# kiln_rpi_breakout_atmega328.net
KiCad netlist of a schematic drawn in EAGLE
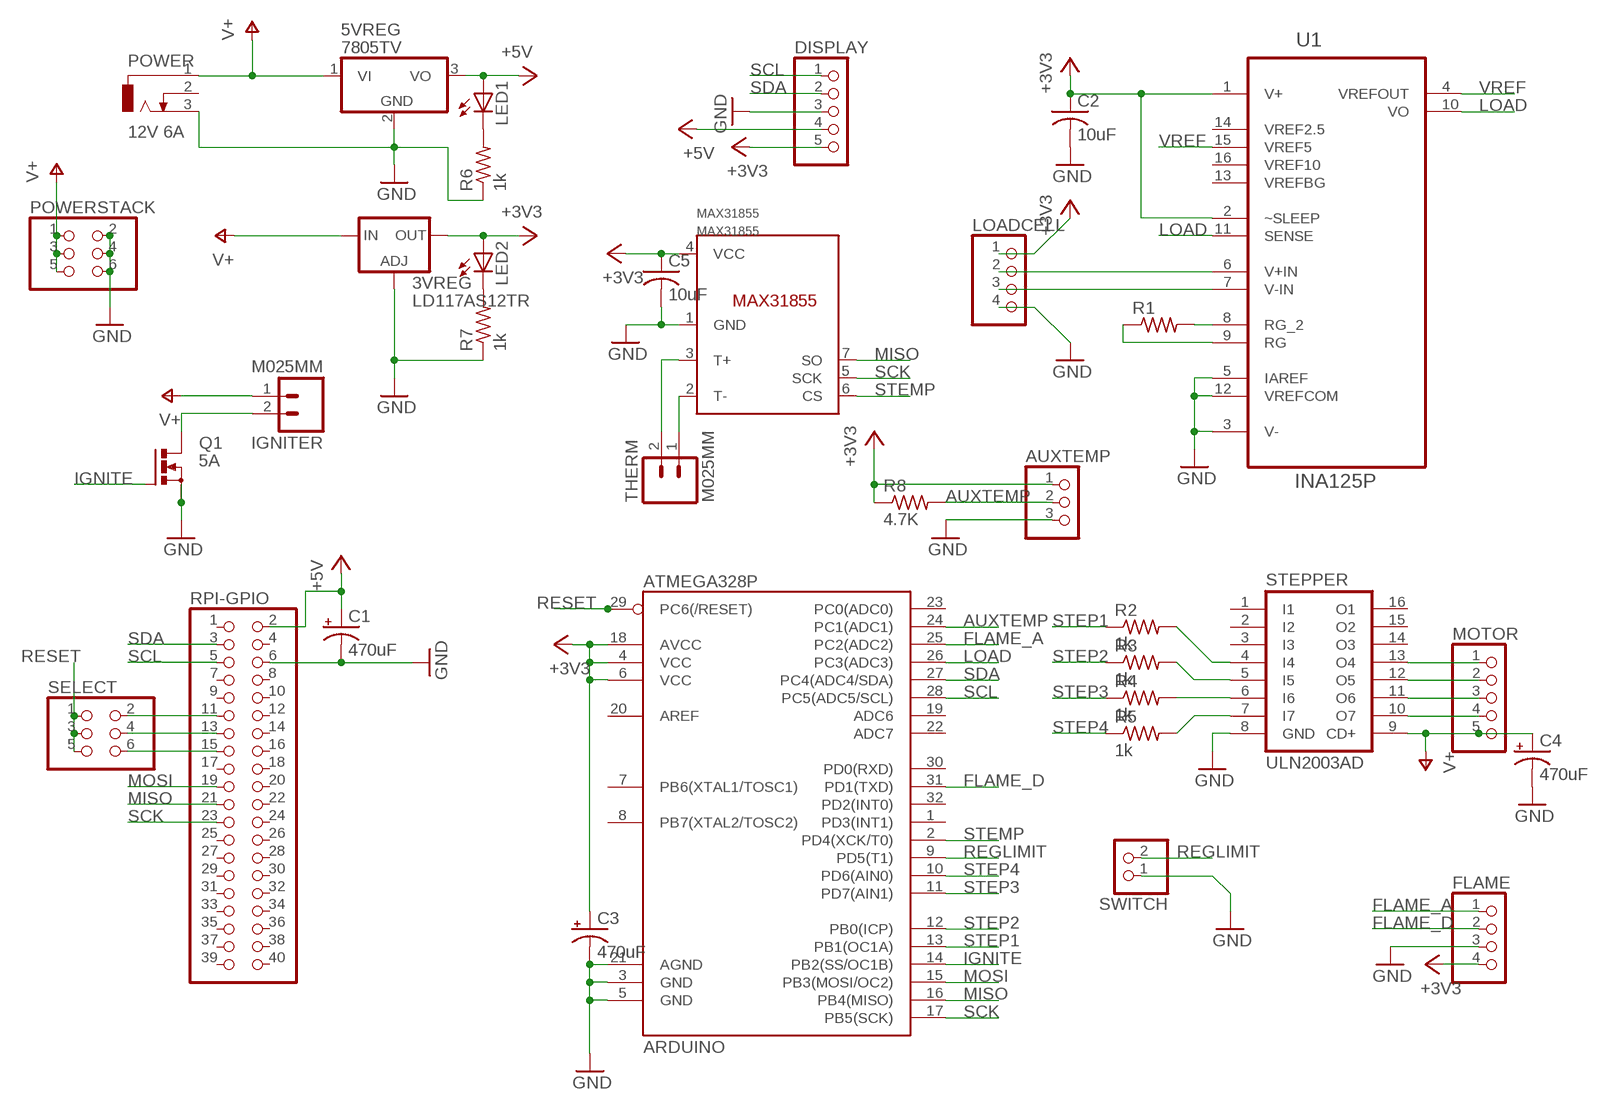
[diagram p0: schematic, sheet 1]

(export (version "E")
  (design (tool "Eeschema 10.0.6"))
  (components
    (comp (ref "3VREG")
      (value "LD117AS12TR")
      (footprint "eagle-import:SOT223")
      (libsource (lib "eagle-import") (part "LD117A?S12TR"))
    )
    (comp (ref "5VREG")
      (value "7805TV")
      (footprint "eagle-import:TO220V")
      (libsource (lib "eagle-import") (part "78TV05"))
    )
    (comp (ref "ARDUINO")
      (value "ATMEGA328P")
      (footprint "eagle-import:TQFP32-08")
      (libsource (lib "eagle-import") (part "ATMEGA328_SMT"))
    )
    (comp (ref "AUXTEMP")
      (value "PINHD-1X3")
      (footprint "eagle-import:1X03")
      (libsource (lib "eagle-import") (part "PINHD-1X3"))
    )
    (comp (ref "C1")
      (value "470uF")
      (footprint "eagle-import:E3,5-8")
      (libsource (lib "eagle-import") (part "CPOL-USE3.5-8"))
    )
    (comp (ref "C2")
      (value "10uF")
      (footprint "eagle-import:C025-030X050")
      (libsource (lib "eagle-import") (part "C-US025-030X050"))
    )
    (comp (ref "C3")
      (value "470uF")
      (footprint "eagle-import:E3,5-8")
      (libsource (lib "eagle-import") (part "CPOL-USE3.5-8"))
    )
    (comp (ref "C4")
      (value "470uF")
      (footprint "eagle-import:E3,5-8")
      (libsource (lib "eagle-import") (part "CPOL-USE3.5-8"))
    )
    (comp (ref "C5")
      (value "10uF")
      (footprint "eagle-import:C025-030X050")
      (libsource (lib "eagle-import") (part "C-US025-030X050"))
    )
    (comp (ref "DISPLAY")
      (value "PINHD-1X5")
      (footprint "eagle-import:1X05")
      (libsource (lib "eagle-import") (part "PINHD-1X5"))
    )
    (comp (ref "FLAME")
      (value "PINHD-1X4/90")
      (footprint "eagle-import:1X04_90")
      (libsource (lib "eagle-import") (part "PINHD-1X4/90"))
    )
    (comp (ref "IGNITER")
      (value "M025MM")
      (footprint "eagle-import:SCREWTERMINAL-5MM-2")
      (libsource (lib "eagle-import") (part "M025MM"))
    )
    (comp (ref "LED1")
      (value "LED3MM")
      (footprint "eagle-import:LED3MM")
      (libsource (lib "eagle-import") (part "LED3MM"))
    )
    (comp (ref "LED2")
      (value "LED3MM")
      (footprint "eagle-import:LED3MM")
      (libsource (lib "eagle-import") (part "LED3MM"))
    )
    (comp (ref "LOADCELL")
      (value "PINHD-1X4/90")
      (footprint "eagle-import:1X04_90")
      (libsource (lib "eagle-import") (part "PINHD-1X4/90"))
    )
    (comp (ref "MAX31855")
      (value "MAX31855")
      (footprint "eagle-import:SOIC8")
      (libsource (lib "eagle-import") (part "MAX31855"))
    )
    (comp (ref "MOTOR")
      (value "PINHD-1X5/90")
      (footprint "eagle-import:1X05_90")
      (libsource (lib "eagle-import") (part "PINHD-1X5/90"))
    )
    (comp (ref "POWER")
      (value "12V 6A")
      (footprint "eagle-import:DCJ0303")
      (libsource (lib "eagle-import") (part "DCJ0303"))
    )
    (comp (ref "POWERSTACK")
      (value "PINHD-2X3")
      (footprint "eagle-import:2X03")
      (libsource (lib "eagle-import") (part "PINHD-2X3"))
    )
    (comp (ref "Q1")
      (value "5A")
      (footprint "eagle-import:TO220BV")
      (libsource (lib "eagle-import") (part "PMOSFET_NTO220BV"))
    )
    (comp (ref "R1")
      (value "R-US_0204/7")
      (footprint "eagle-import:0204_7")
      (libsource (lib "eagle-import") (part "R-US_0204/7"))
    )
    (comp (ref "R2")
      (value "1k")
      (footprint "eagle-import:0207_7")
      (libsource (lib "eagle-import") (part "R-US_0207/7"))
    )
    (comp (ref "R3")
      (value "1k")
      (footprint "eagle-import:0207_7")
      (libsource (lib "eagle-import") (part "R-US_0207/7"))
    )
    (comp (ref "R4")
      (value "1k")
      (footprint "eagle-import:0207_7")
      (libsource (lib "eagle-import") (part "R-US_0207/7"))
    )
    (comp (ref "R5")
      (value "1k")
      (footprint "eagle-import:0207_7")
      (libsource (lib "eagle-import") (part "R-US_0207/7"))
    )
    (comp (ref "R6")
      (value "1k")
      (footprint "eagle-import:0207_7")
      (libsource (lib "eagle-import") (part "R-US_0207/7"))
    )
    (comp (ref "R7")
      (value "1k")
      (footprint "eagle-import:0207_7")
      (libsource (lib "eagle-import") (part "R-US_0207/7"))
    )
    (comp (ref "R8")
      (value "4.7K")
      (footprint "eagle-import:0207_2V")
      (libsource (lib "eagle-import") (part "R-US_0207/2V"))
    )
    (comp (ref "RPI-GPIO")
      (value "PINHD-2X20")
      (footprint "eagle-import:2X20")
      (libsource (lib "eagle-import") (part "PINHD-2X20"))
    )
    (comp (ref "SELECT")
      (value "PINHD-2X3")
      (footprint "eagle-import:2X03")
      (libsource (lib "eagle-import") (part "PINHD-2X3"))
    )
    (comp (ref "STEPPER")
      (value "ULN2003AD")
      (footprint "eagle-import:SO16")
      (libsource (lib "eagle-import") (part "ULN2003AD"))
    )
    (comp (ref "SWITCH")
      (value "PINHD-1X2/90")
      (footprint "eagle-import:1X02_90")
      (libsource (lib "eagle-import") (part "PINHD-1X2/90"))
    )
    (comp (ref "THERM")
      (value "M025MM")
      (footprint "eagle-import:SCREWTERMINAL-5MM-2")
      (libsource (lib "eagle-import") (part "M025MM"))
    )
    (comp (ref "U1")
      (value "INA125P")
      (footprint "eagle-import:DIP254P762X508-16")
      (libsource (lib "eagle-import") (part "INA125P"))
    )
  )
  (nets
    (net (code "1") (name "+3V3") (class "Default")
      (node (ref "3VREG") (pin "4") (pinfunction "OUT_4") (pintype "passive"))
      (node (ref "ARDUINO") (pin "18") (pinfunction "AVCC_18") (pintype "bidirectional"))
      (node (ref "ARDUINO") (pin "4") (pinfunction "VCC_4") (pintype "bidirectional"))
      (node (ref "ARDUINO") (pin "6") (pinfunction "VCC_6") (pintype "bidirectional"))
      (node (ref "AUXTEMP") (pin "1") (pinfunction "1_1") (pintype "passive"))
      (node (ref "C2") (pin "1") (pinfunction "1_1") (pintype "passive"))
      (node (ref "C3") (pin "+") (pinfunction "+_+") (pintype "passive"))
      (node (ref "C5") (pin "1") (pinfunction "1_1") (pintype "passive"))
      (node (ref "DISPLAY") (pin "5") (pinfunction "5_5") (pintype "passive"))
      (node (ref "FLAME") (pin "4") (pinfunction "4_4") (pintype "passive"))
      (node (ref "LED2") (pin "A") (pinfunction "A_A") (pintype "passive"))
      (node (ref "LOADCELL") (pin "1") (pinfunction "1_1") (pintype "passive"))
      (node (ref "MAX31855") (pin "4") (pinfunction "VCC_4") (pintype "power_in"))
      (node (ref "R8") (pin "1") (pinfunction "1_1") (pintype "passive"))
      (node (ref "U1") (pin "1") (pinfunction "V+_1") (pintype "power_in"))
      (node (ref "U1") (pin "2") (pinfunction "~{SLEEP}_2") (pintype "passive"))
    )
    (net (code "2") (name "+5V") (class "Default")
      (node (ref "5VREG") (pin "3") (pinfunction "VO_3") (pintype "passive"))
      (node (ref "C1") (pin "+") (pinfunction "+_+") (pintype "passive"))
      (node (ref "DISPLAY") (pin "4") (pinfunction "4_4") (pintype "passive"))
      (node (ref "LED1") (pin "A") (pinfunction "A_A") (pintype "passive"))
      (node (ref "RPI-GPIO") (pin "2") (pinfunction "2_2") (pintype "passive"))
    )
    (net (code "3") (name "/AUXTEMP") (class "Default")
      (node (ref "ARDUINO") (pin "24") (pinfunction "PC1(ADC1)_24") (pintype "bidirectional"))
      (node (ref "AUXTEMP") (pin "2") (pinfunction "2_2") (pintype "passive"))
      (node (ref "R8") (pin "2") (pinfunction "2_2") (pintype "passive"))
    )
    (net (code "4") (name "/FLAME_A") (class "Default")
      (node (ref "ARDUINO") (pin "25") (pinfunction "PC2(ADC2)_25") (pintype "bidirectional"))
      (node (ref "FLAME") (pin "1") (pinfunction "1_1") (pintype "passive"))
    )
    (net (code "5") (name "/FLAME_D") (class "Default")
      (node (ref "ARDUINO") (pin "31") (pinfunction "PD1(TXD)_31") (pintype "bidirectional"))
      (node (ref "FLAME") (pin "2") (pinfunction "2_2") (pintype "passive"))
    )
    (net (code "6") (name "/IGNITE") (class "Default")
      (node (ref "ARDUINO") (pin "14") (pinfunction "PB2(SS/OC1B)_14") (pintype "bidirectional"))
      (node (ref "Q1") (pin "G") (pinfunction "G_G") (pintype "passive"))
    )
    (net (code "7") (name "/LOAD") (class "Default")
      (node (ref "ARDUINO") (pin "26") (pinfunction "PC3(ADC3)_26") (pintype "bidirectional"))
      (node (ref "U1") (pin "10") (pinfunction "VO_10") (pintype "output"))
      (node (ref "U1") (pin "11") (pinfunction "SENSE_11") (pintype "input"))
    )
    (net (code "8") (name "/MISO") (class "Default")
      (node (ref "ARDUINO") (pin "16") (pinfunction "PB4(MISO)_16") (pintype "bidirectional"))
      (node (ref "MAX31855") (pin "7") (pinfunction "SO_7") (pintype "output"))
      (node (ref "RPI-GPIO") (pin "21") (pinfunction "21_21") (pintype "passive"))
    )
    (net (code "9") (name "/MOSI") (class "Default")
      (node (ref "ARDUINO") (pin "15") (pinfunction "PB3(MOSI/OC2)_15") (pintype "bidirectional"))
      (node (ref "RPI-GPIO") (pin "19") (pinfunction "19_19") (pintype "passive"))
    )
    (net (code "10") (name "/REGLIMIT") (class "Default")
      (node (ref "ARDUINO") (pin "9") (pinfunction "PD5(T1)_9") (pintype "bidirectional"))
      (node (ref "SWITCH") (pin "2") (pinfunction "2_2") (pintype "passive"))
    )
    (net (code "11") (name "/RESET") (class "Default")
      (node (ref "ARDUINO") (pin "29") (pinfunction "PC6(/RESET)_29") (pintype "bidirectional"))
      (node (ref "SELECT") (pin "1") (pinfunction "1_1") (pintype "passive"))
      (node (ref "SELECT") (pin "3") (pinfunction "3_3") (pintype "passive"))
      (node (ref "SELECT") (pin "5") (pinfunction "5_5") (pintype "passive"))
    )
    (net (code "12") (name "/SCK") (class "Default")
      (node (ref "ARDUINO") (pin "17") (pinfunction "PB5(SCK)_17") (pintype "bidirectional"))
      (node (ref "MAX31855") (pin "5") (pinfunction "SCK_5") (pintype "input"))
      (node (ref "RPI-GPIO") (pin "23") (pinfunction "23_23") (pintype "passive"))
    )
    (net (code "13") (name "/SCL") (class "Default")
      (node (ref "ARDUINO") (pin "28") (pinfunction "PC5(ADC5/SCL)_28") (pintype "bidirectional"))
      (node (ref "DISPLAY") (pin "1") (pinfunction "1_1") (pintype "passive"))
      (node (ref "RPI-GPIO") (pin "5") (pinfunction "5_5") (pintype "passive"))
    )
    (net (code "14") (name "/SDA") (class "Default")
      (node (ref "ARDUINO") (pin "27") (pinfunction "PC4(ADC4/SDA)_27") (pintype "bidirectional"))
      (node (ref "DISPLAY") (pin "2") (pinfunction "2_2") (pintype "passive"))
      (node (ref "RPI-GPIO") (pin "3") (pinfunction "3_3") (pintype "passive"))
    )
    (net (code "15") (name "/STEMP") (class "Default")
      (node (ref "ARDUINO") (pin "2") (pinfunction "PD4(XCK/T0)_2") (pintype "bidirectional"))
      (node (ref "MAX31855") (pin "6") (pinfunction "CS_6") (pintype "input"))
    )
    (net (code "16") (name "/STEP1") (class "Default")
      (node (ref "ARDUINO") (pin "13") (pinfunction "PB1(OC1A)_13") (pintype "bidirectional"))
      (node (ref "R2") (pin "1") (pinfunction "1_1") (pintype "passive"))
    )
    (net (code "17") (name "/STEP2") (class "Default")
      (node (ref "ARDUINO") (pin "12") (pinfunction "PB0(ICP)_12") (pintype "bidirectional"))
      (node (ref "R3") (pin "1") (pinfunction "1_1") (pintype "passive"))
    )
    (net (code "18") (name "/STEP3") (class "Default")
      (node (ref "ARDUINO") (pin "11") (pinfunction "PD7(AIN1)_11") (pintype "bidirectional"))
      (node (ref "R4") (pin "1") (pinfunction "1_1") (pintype "passive"))
    )
    (net (code "19") (name "/STEP4") (class "Default")
      (node (ref "ARDUINO") (pin "10") (pinfunction "PD6(AIN0)_10") (pintype "bidirectional"))
      (node (ref "R5") (pin "1") (pinfunction "1_1") (pintype "passive"))
    )
    (net (code "20") (name "/VREF") (class "Default")
      (node (ref "U1") (pin "15") (pinfunction "VREF5_15") (pintype "power_in"))
      (node (ref "U1") (pin "4") (pinfunction "VREFOUT_4") (pintype "output"))
    )
    (net (code "21") (name "/VREF2.5") (class "Default")
      (node (ref "U1") (pin "14") (pinfunction "VREF2.5_14") (pintype "power_in"))
    )
    (net (code "22") (name "/VREF10") (class "Default")
      (node (ref "U1") (pin "16") (pinfunction "VREF10_16") (pintype "power_in"))
    )
    (net (code "23") (name "/VREFBG") (class "Default")
      (node (ref "U1") (pin "13") (pinfunction "VREFBG_13") (pintype "power_in"))
    )
    (net (code "24") (name "GND") (class "Default")
      (node (ref "3VREG") (pin "1") (pinfunction "ADJ_1") (pintype "input"))
      (node (ref "5VREG") (pin "2") (pinfunction "GND_2") (pintype "passive"))
      (node (ref "ARDUINO") (pin "21") (pinfunction "AGND_21") (pintype "bidirectional"))
      (node (ref "ARDUINO") (pin "3") (pinfunction "GND_3") (pintype "bidirectional"))
      (node (ref "ARDUINO") (pin "5") (pinfunction "GND_5") (pintype "bidirectional"))
      (node (ref "AUXTEMP") (pin "3") (pinfunction "3_3") (pintype "passive"))
      (node (ref "C1") (pin "-") (pinfunction "-_-") (pintype "passive"))
      (node (ref "C2") (pin "2") (pinfunction "2_2") (pintype "passive"))
      (node (ref "C3") (pin "-") (pinfunction "-_-") (pintype "passive"))
      (node (ref "C4") (pin "-") (pinfunction "-_-") (pintype "passive"))
      (node (ref "C5") (pin "2") (pinfunction "2_2") (pintype "passive"))
      (node (ref "DISPLAY") (pin "3") (pinfunction "3_3") (pintype "passive"))
      (node (ref "FLAME") (pin "3") (pinfunction "3_3") (pintype "passive"))
      (node (ref "LOADCELL") (pin "4") (pinfunction "4_4") (pintype "passive"))
      (node (ref "MAX31855") (pin "1") (pinfunction "GND_1") (pintype "power_in"))
      (node (ref "POWER") (pin "3") (pinfunction "3_3") (pintype "passive"))
      (node (ref "POWERSTACK") (pin "2") (pinfunction "2_2") (pintype "passive"))
      (node (ref "POWERSTACK") (pin "4") (pinfunction "4_4") (pintype "passive"))
      (node (ref "POWERSTACK") (pin "6") (pinfunction "6_6") (pintype "passive"))
      (node (ref "Q1") (pin "S") (pinfunction "S_S") (pintype "passive"))
      (node (ref "R6") (pin "1") (pinfunction "1_1") (pintype "passive"))
      (node (ref "R7") (pin "1") (pinfunction "1_1") (pintype "passive"))
      (node (ref "RPI-GPIO") (pin "6") (pinfunction "6_6") (pintype "passive"))
      (node (ref "STEPPER") (pin "8") (pinfunction "GND_8") (pintype "power_in"))
      (node (ref "SWITCH") (pin "1") (pinfunction "1_1") (pintype "passive"))
      (node (ref "U1") (pin "12") (pinfunction "VREFCOM_12") (pintype "passive"))
      (node (ref "U1") (pin "3") (pinfunction "V-_3") (pintype "power_in"))
      (node (ref "U1") (pin "5") (pinfunction "IAREF_5") (pintype "passive"))
    )
    (net (code "25") (name "Net-(IGNITER-Pad2)") (class "Default")
      (node (ref "IGNITER") (pin "2") (pinfunction "2_2") (pintype "passive"))
      (node (ref "Q1") (pin "D") (pinfunction "D_D") (pintype "passive"))
    )
    (net (code "26") (name "Net-(LED1-C)") (class "Default")
      (node (ref "LED1") (pin "K") (pinfunction "C_K") (pintype "passive"))
      (node (ref "R6") (pin "2") (pinfunction "2_2") (pintype "passive"))
    )
    (net (code "27") (name "Net-(LED2-C)") (class "Default")
      (node (ref "LED2") (pin "K") (pinfunction "C_K") (pintype "passive"))
      (node (ref "R7") (pin "2") (pinfunction "2_2") (pintype "passive"))
    )
    (net (code "28") (name "Net-(MAX31855-T+)") (class "Default")
      (node (ref "MAX31855") (pin "3") (pinfunction "T+_3") (pintype "input"))
      (node (ref "THERM") (pin "2") (pinfunction "2_2") (pintype "passive"))
    )
    (net (code "29") (name "Net-(MAX31855-T-)") (class "Default")
      (node (ref "MAX31855") (pin "2") (pinfunction "T-_2") (pintype "input"))
      (node (ref "THERM") (pin "1") (pinfunction "1_1") (pintype "passive"))
    )
    (net (code "30") (name "Net-(RPI-GPIO-Pad11)") (class "Default")
      (node (ref "RPI-GPIO") (pin "11") (pinfunction "11_11") (pintype "passive"))
      (node (ref "SELECT") (pin "2") (pinfunction "2_2") (pintype "passive"))
    )
    (net (code "31") (name "Net-(RPI-GPIO-Pad13)") (class "Default")
      (node (ref "RPI-GPIO") (pin "13") (pinfunction "13_13") (pintype "passive"))
      (node (ref "SELECT") (pin "4") (pinfunction "4_4") (pintype "passive"))
    )
    (net (code "32") (name "Net-(RPI-GPIO-Pad15)") (class "Default")
      (node (ref "RPI-GPIO") (pin "15") (pinfunction "15_15") (pintype "passive"))
      (node (ref "SELECT") (pin "6") (pinfunction "6_6") (pintype "passive"))
    )
    (net (code "33") (name "Net-(STEPPER-I4)") (class "Default")
      (node (ref "R2") (pin "2") (pinfunction "2_2") (pintype "passive"))
      (node (ref "STEPPER") (pin "4") (pinfunction "I4_4") (pintype "input"))
    )
    (net (code "34") (name "Net-(STEPPER-I5)") (class "Default")
      (node (ref "R3") (pin "2") (pinfunction "2_2") (pintype "passive"))
      (node (ref "STEPPER") (pin "5") (pinfunction "I5_5") (pintype "input"))
    )
    (net (code "35") (name "Net-(STEPPER-I6)") (class "Default")
      (node (ref "R4") (pin "2") (pinfunction "2_2") (pintype "passive"))
      (node (ref "STEPPER") (pin "6") (pinfunction "I6_6") (pintype "input"))
    )
    (net (code "36") (name "Net-(STEPPER-I7)") (class "Default")
      (node (ref "R5") (pin "2") (pinfunction "2_2") (pintype "passive"))
      (node (ref "STEPPER") (pin "7") (pinfunction "I7_7") (pintype "input"))
    )
    (net (code "37") (name "Net-(STEPPER-O4)") (class "Default")
      (node (ref "MOTOR") (pin "1") (pinfunction "1_1") (pintype "passive"))
      (node (ref "STEPPER") (pin "13") (pinfunction "O4_13") (pintype "open_collector"))
    )
    (net (code "38") (name "Net-(STEPPER-O5)") (class "Default")
      (node (ref "MOTOR") (pin "2") (pinfunction "2_2") (pintype "passive"))
      (node (ref "STEPPER") (pin "12") (pinfunction "O5_12") (pintype "open_collector"))
    )
    (net (code "39") (name "Net-(STEPPER-O6)") (class "Default")
      (node (ref "MOTOR") (pin "3") (pinfunction "3_3") (pintype "passive"))
      (node (ref "STEPPER") (pin "11") (pinfunction "O6_11") (pintype "open_collector"))
    )
    (net (code "40") (name "Net-(STEPPER-O7)") (class "Default")
      (node (ref "MOTOR") (pin "4") (pinfunction "4_4") (pintype "passive"))
      (node (ref "STEPPER") (pin "10") (pinfunction "O7_10") (pintype "open_collector"))
    )
    (net (code "41") (name "Net-(U1-RG)") (class "Default")
      (node (ref "R1") (pin "1") (pinfunction "1_1") (pintype "passive"))
      (node (ref "U1") (pin "9") (pinfunction "RG_9") (pintype "passive"))
    )
    (net (code "42") (name "Net-(U1-RG_2)") (class "Default")
      (node (ref "R1") (pin "2") (pinfunction "2_2") (pintype "passive"))
      (node (ref "U1") (pin "8") (pinfunction "RG_2_8") (pintype "passive"))
    )
    (net (code "43") (name "Net-(U1-V+IN)") (class "Default")
      (node (ref "LOADCELL") (pin "2") (pinfunction "2_2") (pintype "passive"))
      (node (ref "U1") (pin "6") (pinfunction "V+IN_6") (pintype "power_in"))
    )
    (net (code "44") (name "Net-(U1-V-IN)") (class "Default")
      (node (ref "LOADCELL") (pin "3") (pinfunction "3_3") (pintype "passive"))
      (node (ref "U1") (pin "7") (pinfunction "V-IN_7") (pintype "power_in"))
    )
    (net (code "45") (name "V+") (class "Default")
      (node (ref "3VREG") (pin "3") (pinfunction "IN_3") (pintype "input"))
      (node (ref "5VREG") (pin "1") (pinfunction "VI_1") (pintype "input"))
      (node (ref "C4") (pin "+") (pinfunction "+_+") (pintype "passive"))
      (node (ref "IGNITER") (pin "1") (pinfunction "1_1") (pintype "passive"))
      (node (ref "MOTOR") (pin "5") (pinfunction "5_5") (pintype "passive"))
      (node (ref "POWER") (pin "1") (pinfunction "1_1") (pintype "passive"))
      (node (ref "POWERSTACK") (pin "1") (pinfunction "1_1") (pintype "passive"))
      (node (ref "POWERSTACK") (pin "3") (pinfunction "3_3") (pintype "passive"))
      (node (ref "POWERSTACK") (pin "5") (pinfunction "5_5") (pintype "passive"))
      (node (ref "STEPPER") (pin "9") (pinfunction "CD+_9") (pintype "passive"))
    )
    (net (code "46") (name "unconnected-(ARDUINO-ADC6-Pad19)") (class "Default")
      (node (ref "ARDUINO") (pin "19") (pinfunction "ADC6_19") (pintype "bidirectional"))
    )
    (net (code "47") (name "unconnected-(ARDUINO-ADC7-Pad22)") (class "Default")
      (node (ref "ARDUINO") (pin "22") (pinfunction "ADC7_22") (pintype "bidirectional"))
    )
    (net (code "48") (name "unconnected-(ARDUINO-AREF-Pad20)") (class "Default")
      (node (ref "ARDUINO") (pin "20") (pinfunction "AREF_20") (pintype "bidirectional"))
    )
    (net (code "49") (name "unconnected-(ARDUINO-PB6(XTAL1{slash}TOSC1)-Pad7)") (class "Default")
      (node (ref "ARDUINO") (pin "7") (pinfunction "PB6(XTAL1/TOSC1)_7") (pintype "bidirectional"))
    )
    (net (code "50") (name "unconnected-(ARDUINO-PB7(XTAL2{slash}TOSC2)-Pad8)") (class "Default")
      (node (ref "ARDUINO") (pin "8") (pinfunction "PB7(XTAL2/TOSC2)_8") (pintype "bidirectional"))
    )
    (net (code "51") (name "unconnected-(ARDUINO-PC0(ADC0)-Pad23)") (class "Default")
      (node (ref "ARDUINO") (pin "23") (pinfunction "PC0(ADC0)_23") (pintype "bidirectional"))
    )
    (net (code "52") (name "unconnected-(ARDUINO-PD0(RXD)-Pad30)") (class "Default")
      (node (ref "ARDUINO") (pin "30") (pinfunction "PD0(RXD)_30") (pintype "bidirectional"))
    )
    (net (code "53") (name "unconnected-(ARDUINO-PD2(INT0)-Pad32)") (class "Default")
      (node (ref "ARDUINO") (pin "32") (pinfunction "PD2(INT0)_32") (pintype "bidirectional"))
    )
    (net (code "54") (name "unconnected-(ARDUINO-PD3(INT1)-Pad1)") (class "Default")
      (node (ref "ARDUINO") (pin "1") (pinfunction "PD3(INT1)_1") (pintype "bidirectional"))
    )
    (net (code "55") (name "unconnected-(POWER-Pad2)") (class "Default")
      (node (ref "POWER") (pin "2") (pinfunction "2_2") (pintype "passive"))
    )
    (net (code "56") (name "unconnected-(RPI-GPIO-Pad1)") (class "Default")
      (node (ref "RPI-GPIO") (pin "1") (pinfunction "1_1") (pintype "passive"))
    )
    (net (code "57") (name "unconnected-(RPI-GPIO-Pad4)") (class "Default")
      (node (ref "RPI-GPIO") (pin "4") (pinfunction "4_4") (pintype "passive"))
    )
    (net (code "58") (name "unconnected-(RPI-GPIO-Pad7)") (class "Default")
      (node (ref "RPI-GPIO") (pin "7") (pinfunction "7_7") (pintype "passive"))
    )
    (net (code "59") (name "unconnected-(RPI-GPIO-Pad8)") (class "Default")
      (node (ref "RPI-GPIO") (pin "8") (pinfunction "8_8") (pintype "passive"))
    )
    (net (code "60") (name "unconnected-(RPI-GPIO-Pad9)") (class "Default")
      (node (ref "RPI-GPIO") (pin "9") (pinfunction "9_9") (pintype "passive"))
    )
    (net (code "61") (name "unconnected-(RPI-GPIO-Pad10)") (class "Default")
      (node (ref "RPI-GPIO") (pin "10") (pinfunction "10_10") (pintype "passive"))
    )
    (net (code "62") (name "unconnected-(RPI-GPIO-Pad12)") (class "Default")
      (node (ref "RPI-GPIO") (pin "12") (pinfunction "12_12") (pintype "passive"))
    )
    (net (code "63") (name "unconnected-(RPI-GPIO-Pad14)") (class "Default")
      (node (ref "RPI-GPIO") (pin "14") (pinfunction "14_14") (pintype "passive"))
    )
    (net (code "64") (name "unconnected-(RPI-GPIO-Pad16)") (class "Default")
      (node (ref "RPI-GPIO") (pin "16") (pinfunction "16_16") (pintype "passive"))
    )
    (net (code "65") (name "unconnected-(RPI-GPIO-Pad17)") (class "Default")
      (node (ref "RPI-GPIO") (pin "17") (pinfunction "17_17") (pintype "passive"))
    )
    (net (code "66") (name "unconnected-(RPI-GPIO-Pad18)") (class "Default")
      (node (ref "RPI-GPIO") (pin "18") (pinfunction "18_18") (pintype "passive"))
    )
    (net (code "67") (name "unconnected-(RPI-GPIO-Pad20)") (class "Default")
      (node (ref "RPI-GPIO") (pin "20") (pinfunction "20_20") (pintype "passive"))
    )
    (net (code "68") (name "unconnected-(RPI-GPIO-Pad22)") (class "Default")
      (node (ref "RPI-GPIO") (pin "22") (pinfunction "22_22") (pintype "passive"))
    )
    (net (code "69") (name "unconnected-(RPI-GPIO-Pad24)") (class "Default")
      (node (ref "RPI-GPIO") (pin "24") (pinfunction "24_24") (pintype "passive"))
    )
    (net (code "70") (name "unconnected-(RPI-GPIO-Pad25)") (class "Default")
      (node (ref "RPI-GPIO") (pin "25") (pinfunction "25_25") (pintype "passive"))
    )
    (net (code "71") (name "unconnected-(RPI-GPIO-Pad26)") (class "Default")
      (node (ref "RPI-GPIO") (pin "26") (pinfunction "26_26") (pintype "passive"))
    )
    (net (code "72") (name "unconnected-(RPI-GPIO-Pad27)") (class "Default")
      (node (ref "RPI-GPIO") (pin "27") (pinfunction "27_27") (pintype "passive"))
    )
    (net (code "73") (name "unconnected-(RPI-GPIO-Pad28)") (class "Default")
      (node (ref "RPI-GPIO") (pin "28") (pinfunction "28_28") (pintype "passive"))
    )
    (net (code "74") (name "unconnected-(RPI-GPIO-Pad29)") (class "Default")
      (node (ref "RPI-GPIO") (pin "29") (pinfunction "29_29") (pintype "passive"))
    )
    (net (code "75") (name "unconnected-(RPI-GPIO-Pad30)") (class "Default")
      (node (ref "RPI-GPIO") (pin "30") (pinfunction "30_30") (pintype "passive"))
    )
    (net (code "76") (name "unconnected-(RPI-GPIO-Pad31)") (class "Default")
      (node (ref "RPI-GPIO") (pin "31") (pinfunction "31_31") (pintype "passive"))
    )
    (net (code "77") (name "unconnected-(RPI-GPIO-Pad32)") (class "Default")
      (node (ref "RPI-GPIO") (pin "32") (pinfunction "32_32") (pintype "passive"))
    )
    (net (code "78") (name "unconnected-(RPI-GPIO-Pad33)") (class "Default")
      (node (ref "RPI-GPIO") (pin "33") (pinfunction "33_33") (pintype "passive"))
    )
    (net (code "79") (name "unconnected-(RPI-GPIO-Pad34)") (class "Default")
      (node (ref "RPI-GPIO") (pin "34") (pinfunction "34_34") (pintype "passive"))
    )
    (net (code "80") (name "unconnected-(RPI-GPIO-Pad35)") (class "Default")
      (node (ref "RPI-GPIO") (pin "35") (pinfunction "35_35") (pintype "passive"))
    )
    (net (code "81") (name "unconnected-(RPI-GPIO-Pad36)") (class "Default")
      (node (ref "RPI-GPIO") (pin "36") (pinfunction "36_36") (pintype "passive"))
    )
    (net (code "82") (name "unconnected-(RPI-GPIO-Pad37)") (class "Default")
      (node (ref "RPI-GPIO") (pin "37") (pinfunction "37_37") (pintype "passive"))
    )
    (net (code "83") (name "unconnected-(RPI-GPIO-Pad38)") (class "Default")
      (node (ref "RPI-GPIO") (pin "38") (pinfunction "38_38") (pintype "passive"))
    )
    (net (code "84") (name "unconnected-(RPI-GPIO-Pad39)") (class "Default")
      (node (ref "RPI-GPIO") (pin "39") (pinfunction "39_39") (pintype "passive"))
    )
    (net (code "85") (name "unconnected-(RPI-GPIO-Pad40)") (class "Default")
      (node (ref "RPI-GPIO") (pin "40") (pinfunction "40_40") (pintype "passive"))
    )
    (net (code "86") (name "unconnected-(STEPPER-I1-Pad1)") (class "Default")
      (node (ref "STEPPER") (pin "1") (pinfunction "I1_1") (pintype "input"))
    )
    (net (code "87") (name "unconnected-(STEPPER-I2-Pad2)") (class "Default")
      (node (ref "STEPPER") (pin "2") (pinfunction "I2_2") (pintype "input"))
    )
    (net (code "88") (name "unconnected-(STEPPER-I3-Pad3)") (class "Default")
      (node (ref "STEPPER") (pin "3") (pinfunction "I3_3") (pintype "input"))
    )
    (net (code "89") (name "unconnected-(STEPPER-O1-Pad16)") (class "Default")
      (node (ref "STEPPER") (pin "16") (pinfunction "O1_16") (pintype "open_collector"))
    )
    (net (code "90") (name "unconnected-(STEPPER-O2-Pad15)") (class "Default")
      (node (ref "STEPPER") (pin "15") (pinfunction "O2_15") (pintype "open_collector"))
    )
    (net (code "91") (name "unconnected-(STEPPER-O3-Pad14)") (class "Default")
      (node (ref "STEPPER") (pin "14") (pinfunction "O3_14") (pintype "open_collector"))
    )
  )
)
